# DAC.net
KiCad netlist of a schematic drawn in Altium Designer
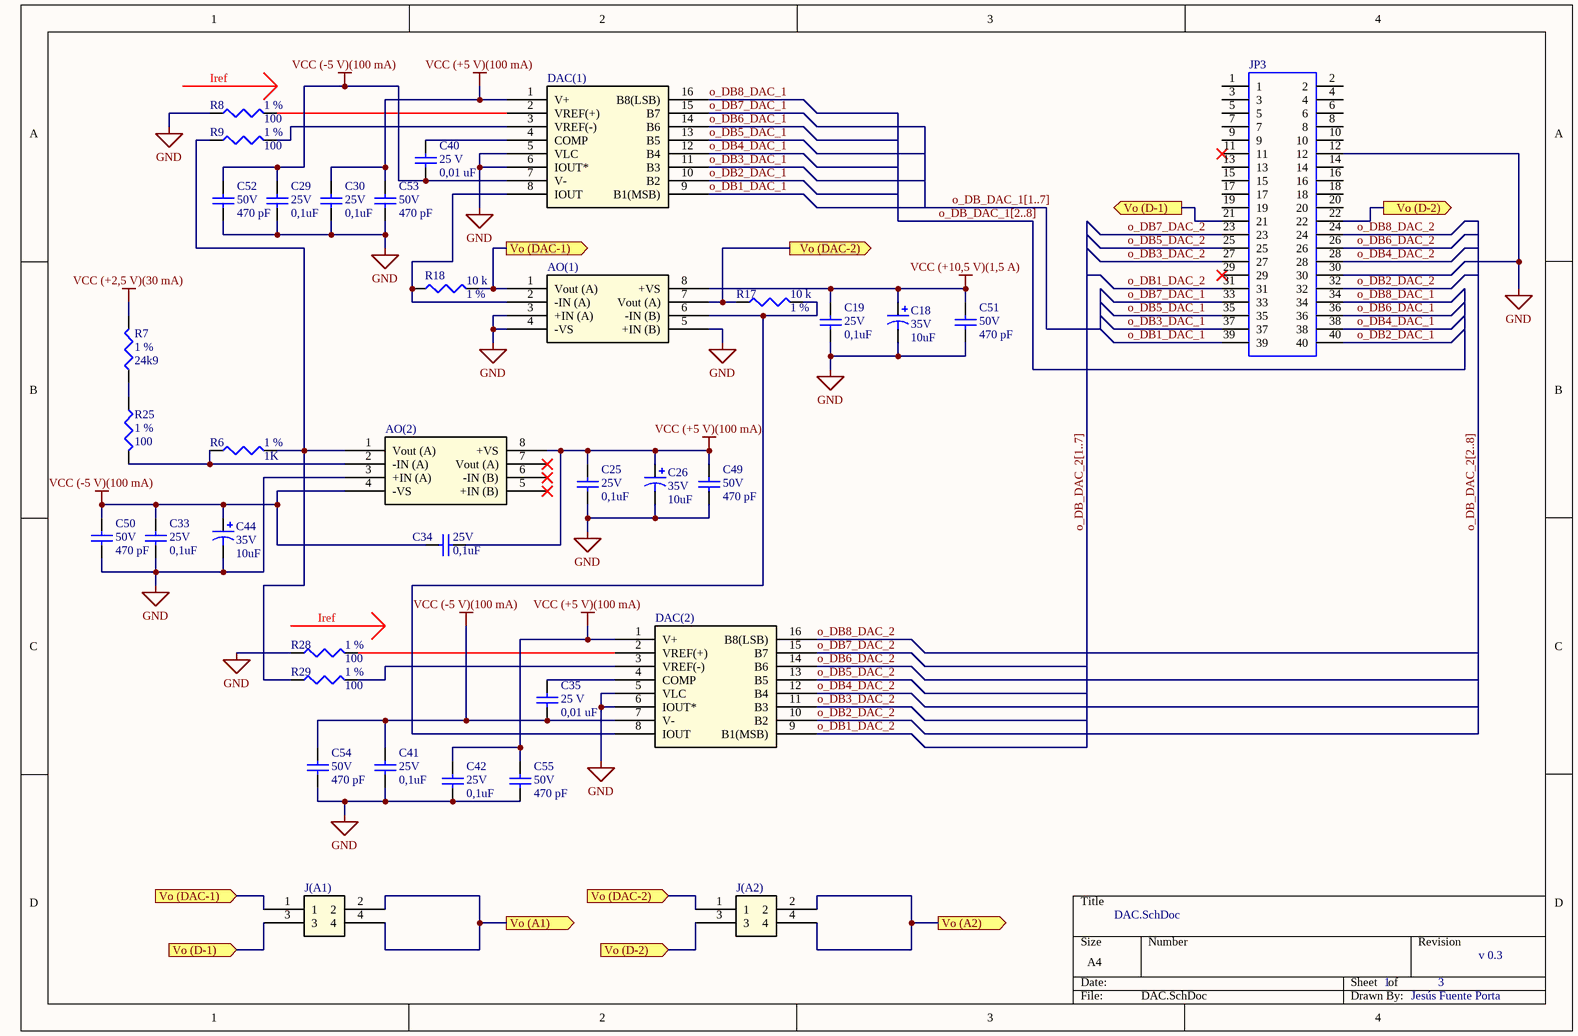
[diagram p0: DAC.SchDoc]

(export (version "E")
  (design (tool "Eeschema 10.0.6"))
  (components
    (comp (ref "AO(1)")
      (value "Part Number: AD8028ARZ")
      (footprint "AD8028ARZ - (R_8-M)")
      (fields
        (field (name "MANUFACTURER_PART_NUMBER") "AD8028ARZ")
        (field (name "COPYRIGHT") "Copyright (C) 2018 Accelerated Designs. All rights reserved")
      )
      (libsource (lib "ADC Library") (part "AD8028ARZ"))
    )
    (comp (ref "AO(2)")
      (value "Part Number: AD8028ARZ")
      (footprint "AD8028ARZ - (R_8-M)")
      (fields
        (field (name "MANUFACTURER_PART_NUMBER") "AD8028ARZ")
        (field (name "COPYRIGHT") "Copyright (C) 2018 Accelerated Designs. All rights reserved")
      )
      (libsource (lib "ADC Library") (part "AD8028ARZ"))
    )
    (comp (ref "C18")
      (value "35V")
      (footprint "EEE1VA100WR")
      (fields (field (name "ALTIUM_VALUE") "10uF") (field (name "PUBLISHER") "Altium Limited"))
      (libsource (lib "Miscellaneous Devices") (part "Cap Pol3"))
    )
    (comp (ref "C19")
      (value "25V")
      (footprint "1206 [Métrica 3216]")
      (fields (field (name "ALTIUM_VALUE") "0,1uF") (field (name "PUBLISHER") "Altium Limited"))
      (libsource (lib "Miscellaneous Devices") (part "Cap Semi"))
    )
    (comp (ref "C25")
      (value "25V")
      (footprint "1206 [Métrica 3216]")
      (fields (field (name "ALTIUM_VALUE") "0,1uF") (field (name "PUBLISHER") "Altium Limited"))
      (libsource (lib "Miscellaneous Devices") (part "Cap Semi"))
    )
    (comp (ref "C26")
      (value "35V")
      (footprint "EEE1VA100WR")
      (fields (field (name "ALTIUM_VALUE") "10uF") (field (name "PUBLISHER") "Altium Limited"))
      (libsource (lib "Miscellaneous Devices") (part "Cap Pol3"))
    )
    (comp (ref "C29")
      (value "25V")
      (footprint "1206 [Métrica 3216]")
      (fields (field (name "ALTIUM_VALUE") "0,1uF") (field (name "PUBLISHER") "Altium Limited"))
      (libsource (lib "Miscellaneous Devices") (part "Cap Semi"))
    )
    (comp (ref "C30")
      (value "25V")
      (footprint "1206 [Métrica 3216]")
      (fields (field (name "ALTIUM_VALUE") "0,1uF") (field (name "PUBLISHER") "Altium Limited"))
      (libsource (lib "Miscellaneous Devices") (part "Cap Semi"))
    )
    (comp (ref "C33")
      (value "25V")
      (footprint "1206 [Métrica 3216]")
      (fields (field (name "ALTIUM_VALUE") "0,1uF") (field (name "PUBLISHER") "Altium Limited"))
      (libsource (lib "Miscellaneous Devices") (part "Cap Semi"))
    )
    (comp (ref "C34")
      (value "25V")
      (footprint "1206 [Métrica 3216]")
      (fields (field (name "ALTIUM_VALUE") "0,1uF") (field (name "PUBLISHER") "Altium Limited"))
      (libsource (lib "Miscellaneous Devices") (part "Cap Semi"))
    )
    (comp (ref "C35")
      (value "25 V")
      (footprint "1206 [Métrica 3216]")
      (fields (field (name "ALTIUM_VALUE") "0,01 uF") (field (name "PUBLISHER") "Altium Limited"))
      (libsource (lib "Miscellaneous Devices") (part "Cap Semi"))
    )
    (comp (ref "C40")
      (value "25 V")
      (footprint "1206 [Métrica 3216]")
      (fields (field (name "ALTIUM_VALUE") "0,01 uF") (field (name "PUBLISHER") "Altium Limited"))
      (libsource (lib "Miscellaneous Devices") (part "Cap Semi"))
    )
    (comp (ref "C41")
      (value "25V")
      (footprint "1206 [Métrica 3216]")
      (fields (field (name "ALTIUM_VALUE") "0,1uF") (field (name "PUBLISHER") "Altium Limited"))
      (libsource (lib "Miscellaneous Devices") (part "Cap Semi"))
    )
    (comp (ref "C42")
      (value "25V")
      (footprint "1206 [Métrica 3216]")
      (fields (field (name "ALTIUM_VALUE") "0,1uF") (field (name "PUBLISHER") "Altium Limited"))
      (libsource (lib "Miscellaneous Devices") (part "Cap Semi"))
    )
    (comp (ref "C44")
      (value "35V")
      (footprint "EEE1VA100WR")
      (fields (field (name "ALTIUM_VALUE") "10uF") (field (name "PUBLISHER") "Altium Limited"))
      (libsource (lib "Miscellaneous Devices") (part "Cap Pol3"))
    )
    (comp (ref "C49")
      (value "50V")
      (footprint "1206 [Métrica 3216]")
      (fields (field (name "ALTIUM_VALUE") "470 pF") (field (name "PUBLISHER") "Altium Limited"))
      (libsource (lib "Miscellaneous Devices") (part "Cap Semi"))
    )
    (comp (ref "C50")
      (value "50V")
      (footprint "1206 [Métrica 3216]")
      (fields (field (name "ALTIUM_VALUE") "470 pF") (field (name "PUBLISHER") "Altium Limited"))
      (libsource (lib "Miscellaneous Devices") (part "Cap Semi"))
    )
    (comp (ref "C51")
      (value "50V")
      (footprint "1206 [Métrica 3216]")
      (fields (field (name "ALTIUM_VALUE") "470 pF") (field (name "PUBLISHER") "Altium Limited"))
      (libsource (lib "Miscellaneous Devices") (part "Cap Semi"))
    )
    (comp (ref "C52")
      (value "50V")
      (footprint "1206 [Métrica 3216]")
      (fields (field (name "ALTIUM_VALUE") "470 pF") (field (name "PUBLISHER") "Altium Limited"))
      (libsource (lib "Miscellaneous Devices") (part "Cap Semi"))
    )
    (comp (ref "C53")
      (value "50V")
      (footprint "1206 [Métrica 3216]")
      (fields (field (name "ALTIUM_VALUE") "470 pF") (field (name "PUBLISHER") "Altium Limited"))
      (libsource (lib "Miscellaneous Devices") (part "Cap Semi"))
    )
    (comp (ref "C54")
      (value "50V")
      (footprint "1206 [Métrica 3216]")
      (fields (field (name "ALTIUM_VALUE") "470 pF") (field (name "PUBLISHER") "Altium Limited"))
      (libsource (lib "Miscellaneous Devices") (part "Cap Semi"))
    )
    (comp (ref "C55")
      (value "50V")
      (footprint "1206 [Métrica 3216]")
      (fields (field (name "ALTIUM_VALUE") "470 pF") (field (name "PUBLISHER") "Altium Limited"))
      (libsource (lib "Miscellaneous Devices") (part "Cap Semi"))
    )
    (comp (ref "DAC(1)")
      (value "Part Number: DAC08ESZ")
      (footprint "DAC08ESZ_(R_16-M)")
      (description "DAC08ESZ -  Convertidor de Señal Digital a Analógica, 8 bit, ± 4.5V a ± 18V, NSOIC, 16 Pines")
      (fields
        (field (name "MANUFACTURER_PART_NUMBER") "DAC08ESZ")
        (field (name "COPYRIGHT") "Copyright (C) 2018 Accelerated Designs. All rights reserved")
      )
      (libsource (lib "ADC Library") (part "DAC08ESZ"))
    )
    (comp (ref "DAC(2)")
      (value "Part Number: DAC08ESZ")
      (footprint "DAC08ESZ_(R_16-M)")
      (description "DAC08ESZ -  Convertidor de Señal Digital a Analógica, 8 bit, ± 4.5V a ± 18V, NSOIC, 16 Pines")
      (fields
        (field (name "MANUFACTURER_PART_NUMBER") "DAC08ESZ")
        (field (name "COPYRIGHT") "Copyright (C) 2018 Accelerated Designs. All rights reserved")
      )
      (libsource (lib "ADC Library") (part "DAC08ESZ"))
    )
    (comp (ref "J(A1)")
      (value "TMM-102-01-G-D00 (2 connectors)")
      (footprint "TMM-102-01-G-D00 (2 connectors)")
      (fields
        (field (name "MANUFACTURER_PART_NUMBER") "TMM-102-01-L-D-SM")
        (field (name "COPYRIGHT") "Copyright (C) 2018 Accelerated Designs. All rights reserved")
      )
      (libsource (lib "ADC Library_Schematic Symbols") (part "TMM-102-01-G-D00 (2 connectors)"))
    )
    (comp (ref "J(A2)")
      (value "TMM-102-01-G-D00 (2 connectors)")
      (footprint "TMM-102-01-G-D00 (2 connectors)")
      (fields
        (field (name "MANUFACTURER_PART_NUMBER") "TMM-102-01-L-D-SM")
        (field (name "COPYRIGHT") "Copyright (C) 2018 Accelerated Designs. All rights reserved")
      )
      (libsource (lib "ADC Library_Schematic Symbols") (part "TMM-102-01-G-D00 (2 connectors)"))
    )
    (comp (ref "JP3")
      (value "IDC Connector_40p")
      (footprint "IDC Connector - 40 pins")
      (fields (field (name "RS PART NUMBER") "6257296"))
      (libsource (lib "ADC Library") (part "IDC Connector_40p"))
    )
    (comp (ref "R6")
      (value "1 %")
      (footprint "1206 [Métrica 3216]")
      (fields (field (name "ALTIUM_VALUE") "1K") (field (name "PUBLISHER") "Altium Limited"))
      (libsource (lib "Miscellaneous Devices") (part "Res3"))
    )
    (comp (ref "R7")
      (value "1 %")
      (footprint "1206 [Métrica 3216]")
      (fields (field (name "ALTIUM_VALUE") "24k9") (field (name "PUBLISHER") "Altium Limited"))
      (libsource (lib "Miscellaneous Devices") (part "Res3"))
    )
    (comp (ref "R8")
      (value "1 %")
      (footprint "1206 [Métrica 3216]")
      (fields (field (name "ALTIUM_VALUE") "100") (field (name "PUBLISHER") "Altium Limited"))
      (libsource (lib "Miscellaneous Devices") (part "Res3"))
    )
    (comp (ref "R9")
      (value "1 %")
      (footprint "1206 [Métrica 3216]")
      (fields (field (name "ALTIUM_VALUE") "100") (field (name "PUBLISHER") "Altium Limited"))
      (libsource (lib "Miscellaneous Devices") (part "Res3"))
    )
    (comp (ref "R17")
      (value "1 %")
      (footprint "1206 [Métrica 3216]")
      (fields (field (name "ALTIUM_VALUE") "10 k") (field (name "PUBLISHER") "Altium Limited"))
      (libsource (lib "Miscellaneous Devices") (part "Res3"))
    )
    (comp (ref "R18")
      (value "1 %")
      (footprint "1206 [Métrica 3216]")
      (fields (field (name "ALTIUM_VALUE") "10 k") (field (name "PUBLISHER") "Altium Limited"))
      (libsource (lib "Miscellaneous Devices") (part "Res3"))
    )
    (comp (ref "R25")
      (value "1 %")
      (footprint "1206 [Métrica 3216]")
      (fields (field (name "ALTIUM_VALUE") "100") (field (name "PUBLISHER") "Altium Limited"))
      (libsource (lib "Miscellaneous Devices") (part "Res3"))
    )
    (comp (ref "R28")
      (value "1 %")
      (footprint "1206 [Métrica 3216]")
      (fields (field (name "ALTIUM_VALUE") "100") (field (name "PUBLISHER") "Altium Limited"))
      (libsource (lib "Miscellaneous Devices") (part "Res3"))
    )
    (comp (ref "R29")
      (value "1 %")
      (footprint "1206 [Métrica 3216]")
      (fields (field (name "ALTIUM_VALUE") "100") (field (name "PUBLISHER") "Altium Limited"))
      (libsource (lib "Miscellaneous Devices") (part "Res3"))
    )
  )
  (nets
    (net (code "17") (name "/Vo (A1)") (class "Default")
      (node (ref "J(A1)") (pin "2") (pinfunction "2_2") (pintype "passive"))
      (node (ref "J(A1)") (pin "4") (pinfunction "4_4") (pintype "passive"))
    )
    (net (code "18") (name "/Vo (A2)") (class "Default")
      (node (ref "J(A2)") (pin "2") (pinfunction "2_2") (pintype "passive"))
      (node (ref "J(A2)") (pin "4") (pinfunction "4_4") (pintype "passive"))
    )
    (net (code "19") (name "/Vo (D-1)") (class "Default")
      (node (ref "J(A1)") (pin "3") (pinfunction "3_3") (pintype "passive"))
      (node (ref "JP3") (pin "21") (pinfunction "21_21") (pintype "passive"))
    )
    (net (code "20") (name "/Vo (D-2)") (class "Default")
      (node (ref "J(A2)") (pin "3") (pinfunction "3_3") (pintype "passive"))
      (node (ref "JP3") (pin "22") (pinfunction "22_22") (pintype "passive"))
    )
    (net (code "21") (name "/Vo (DAC-1)") (class "Default")
      (node (ref "AO(1)") (pin "1") (pinfunction "Vout_(A)_1") (pintype "passive"))
      (node (ref "J(A1)") (pin "1") (pinfunction "1_1") (pintype "passive"))
      (node (ref "R18") (pin "2") (pinfunction "2_2") (pintype "passive"))
    )
    (net (code "22") (name "/Vo (DAC-2)") (class "Default")
      (node (ref "AO(1)") (pin "7") (pinfunction "Vout_(A)_7") (pintype "passive"))
      (node (ref "J(A2)") (pin "1") (pinfunction "1_1") (pintype "passive"))
      (node (ref "R17") (pin "1") (pinfunction "1_1") (pintype "passive"))
    )
    (net (code "23") (name "/o_DB1_DAC_1") (class "Default")
      (node (ref "DAC(1)") (pin "9") (pinfunction "B1(MSB)_9") (pintype "passive"))
      (node (ref "JP3") (pin "39") (pinfunction "39_39") (pintype "passive"))
    )
    (net (code "24") (name "/o_DB1_DAC_2") (class "Default")
      (node (ref "DAC(2)") (pin "9") (pinfunction "B1(MSB)_9") (pintype "passive"))
      (node (ref "JP3") (pin "31") (pinfunction "31_31") (pintype "passive"))
    )
    (net (code "25") (name "/o_DB2_DAC_1") (class "Default")
      (node (ref "DAC(1)") (pin "10") (pinfunction "B2_10") (pintype "passive"))
      (node (ref "JP3") (pin "40") (pinfunction "40_40") (pintype "passive"))
    )
    (net (code "26") (name "/o_DB2_DAC_2") (class "Default")
      (node (ref "DAC(2)") (pin "10") (pinfunction "B2_10") (pintype "passive"))
      (node (ref "JP3") (pin "32") (pinfunction "32_32") (pintype "passive"))
    )
    (net (code "27") (name "/o_DB3_DAC_1") (class "Default")
      (node (ref "DAC(1)") (pin "11") (pinfunction "B3_11") (pintype "passive"))
      (node (ref "JP3") (pin "37") (pinfunction "37_37") (pintype "passive"))
    )
    (net (code "28") (name "/o_DB3_DAC_2") (class "Default")
      (node (ref "DAC(2)") (pin "11") (pinfunction "B3_11") (pintype "passive"))
      (node (ref "JP3") (pin "27") (pinfunction "27_27") (pintype "passive"))
    )
    (net (code "29") (name "/o_DB4_DAC_1") (class "Default")
      (node (ref "DAC(1)") (pin "12") (pinfunction "B4_12") (pintype "passive"))
      (node (ref "JP3") (pin "38") (pinfunction "38_38") (pintype "passive"))
    )
    (net (code "30") (name "/o_DB4_DAC_2") (class "Default")
      (node (ref "DAC(2)") (pin "12") (pinfunction "B4_12") (pintype "passive"))
      (node (ref "JP3") (pin "28") (pinfunction "28_28") (pintype "passive"))
    )
    (net (code "31") (name "/o_DB5_DAC_1") (class "Default")
      (node (ref "DAC(1)") (pin "13") (pinfunction "B5_13") (pintype "passive"))
      (node (ref "JP3") (pin "35") (pinfunction "35_35") (pintype "passive"))
    )
    (net (code "32") (name "/o_DB5_DAC_2") (class "Default")
      (node (ref "DAC(2)") (pin "13") (pinfunction "B5_13") (pintype "passive"))
      (node (ref "JP3") (pin "25") (pinfunction "25_25") (pintype "passive"))
    )
    (net (code "33") (name "/o_DB6_DAC_1") (class "Default")
      (node (ref "DAC(1)") (pin "14") (pinfunction "B6_14") (pintype "passive"))
      (node (ref "JP3") (pin "36") (pinfunction "36_36") (pintype "passive"))
    )
    (net (code "34") (name "/o_DB6_DAC_2") (class "Default")
      (node (ref "DAC(2)") (pin "14") (pinfunction "B6_14") (pintype "passive"))
      (node (ref "JP3") (pin "26") (pinfunction "26_26") (pintype "passive"))
    )
    (net (code "35") (name "/o_DB7_DAC_1") (class "Default")
      (node (ref "DAC(1)") (pin "15") (pinfunction "B7_15") (pintype "passive"))
      (node (ref "JP3") (pin "33") (pinfunction "33_33") (pintype "passive"))
    )
    (net (code "36") (name "/o_DB7_DAC_2") (class "Default")
      (node (ref "DAC(2)") (pin "15") (pinfunction "B7_15") (pintype "passive"))
      (node (ref "JP3") (pin "23") (pinfunction "23_23") (pintype "passive"))
    )
    (net (code "37") (name "/o_DB8_DAC_1") (class "Default")
      (node (ref "DAC(1)") (pin "16") (pinfunction "B8(LSB)_16") (pintype "passive"))
      (node (ref "JP3") (pin "34") (pinfunction "34_34") (pintype "passive"))
    )
    (net (code "38") (name "/o_DB8_DAC_2") (class "Default")
      (node (ref "DAC(2)") (pin "16") (pinfunction "B8(LSB)_16") (pintype "passive"))
      (node (ref "JP3") (pin "24") (pinfunction "24_24") (pintype "passive"))
    )
    (net (code "43") (name "GND") (class "Default")
      (node (ref "AO(1)") (pin "3") (pinfunction "+IN_(A)_3") (pintype "passive"))
      (node (ref "AO(1)") (pin "4") (pinfunction "-VS_4") (pintype "power_in"))
      (node (ref "AO(1)") (pin "5") (pinfunction "+IN_(B)_5") (pintype "passive"))
      (node (ref "AO(2)") (pin "3") (pinfunction "+IN_(A)_3") (pintype "passive"))
      (node (ref "C18") (pin "2") (pinfunction "2_2") (pintype "passive"))
      (node (ref "C19") (pin "1") (pinfunction "1_1") (pintype "passive"))
      (node (ref "C25") (pin "1") (pinfunction "1_1") (pintype "passive"))
      (node (ref "C26") (pin "2") (pinfunction "2_2") (pintype "passive"))
      (node (ref "C29") (pin "1") (pinfunction "1_1") (pintype "passive"))
      (node (ref "C30") (pin "1") (pinfunction "1_1") (pintype "passive"))
      (node (ref "C33") (pin "1") (pinfunction "1_1") (pintype "passive"))
      (node (ref "C41") (pin "1") (pinfunction "1_1") (pintype "passive"))
      (node (ref "C42") (pin "1") (pinfunction "1_1") (pintype "passive"))
      (node (ref "C44") (pin "2") (pinfunction "2_2") (pintype "passive"))
      (node (ref "C49") (pin "1") (pinfunction "1_1") (pintype "passive"))
      (node (ref "C50") (pin "1") (pinfunction "1_1") (pintype "passive"))
      (node (ref "C51") (pin "1") (pinfunction "1_1") (pintype "passive"))
      (node (ref "C52") (pin "1") (pinfunction "1_1") (pintype "passive"))
      (node (ref "C53") (pin "1") (pinfunction "1_1") (pintype "passive"))
      (node (ref "C54") (pin "1") (pinfunction "1_1") (pintype "passive"))
      (node (ref "C55") (pin "1") (pinfunction "1_1") (pintype "passive"))
      (node (ref "DAC(1)") (pin "5") (pinfunction "VLC_5") (pintype "passive"))
      (node (ref "DAC(1)") (pin "6") (pinfunction "IOUT*_6") (pintype "passive"))
      (node (ref "DAC(2)") (pin "5") (pinfunction "VLC_5") (pintype "passive"))
      (node (ref "DAC(2)") (pin "6") (pinfunction "IOUT*_6") (pintype "passive"))
      (node (ref "JP3") (pin "12") (pinfunction "12_12") (pintype "passive"))
      (node (ref "JP3") (pin "30") (pinfunction "30_30") (pintype "passive"))
      (node (ref "R28") (pin "1") (pinfunction "1_1") (pintype "passive"))
      (node (ref "R8") (pin "1") (pinfunction "1_1") (pintype "passive"))
    )
    (net (code "44") (name "Net-(AO(1)--IN_(A))") (class "Default")
      (node (ref "AO(1)") (pin "2") (pinfunction "-IN_(A)_2") (pintype "passive"))
      (node (ref "DAC(1)") (pin "8") (pinfunction "IOUT_8") (pintype "passive"))
      (node (ref "R18") (pin "1") (pinfunction "1_1") (pintype "passive"))
    )
    (net (code "45") (name "Net-(AO(1)--IN_(B))") (class "Default")
      (node (ref "AO(1)") (pin "6") (pinfunction "-IN_(B)_6") (pintype "passive"))
      (node (ref "DAC(2)") (pin "8") (pinfunction "IOUT_8") (pintype "passive"))
      (node (ref "R17") (pin "2") (pinfunction "2_2") (pintype "passive"))
    )
    (net (code "46") (name "Net-(AO(2)--IN_(A))") (class "Default")
      (node (ref "AO(2)") (pin "2") (pinfunction "-IN_(A)_2") (pintype "passive"))
      (node (ref "R25") (pin "2") (pinfunction "2_2") (pintype "passive"))
      (node (ref "R6") (pin "1") (pinfunction "1_1") (pintype "passive"))
    )
    (net (code "47") (name "Net-(AO(2)-Vout_(A)-Pad1)") (class "Default")
      (node (ref "AO(2)") (pin "1") (pinfunction "Vout_(A)_1") (pintype "passive"))
      (node (ref "R29") (pin "1") (pinfunction "1_1") (pintype "passive"))
      (node (ref "R6") (pin "2") (pinfunction "2_2") (pintype "passive"))
      (node (ref "R9") (pin "1") (pinfunction "1_1") (pintype "passive"))
    )
    (net (code "48") (name "Net-(DAC(1)-COMP)") (class "Default")
      (node (ref "C40") (pin "2") (pinfunction "2_2") (pintype "passive"))
      (node (ref "DAC(1)") (pin "4") (pinfunction "COMP_4") (pintype "passive"))
    )
    (net (code "49") (name "Net-(DAC(1)-VREF(+))") (class "Default")
      (node (ref "DAC(1)") (pin "2") (pinfunction "VREF(+)_2") (pintype "passive"))
      (node (ref "R8") (pin "2") (pinfunction "2_2") (pintype "passive"))
    )
    (net (code "50") (name "Net-(DAC(1)-VREF(-))") (class "Default")
      (node (ref "DAC(1)") (pin "3") (pinfunction "VREF(-)_3") (pintype "passive"))
      (node (ref "R9") (pin "2") (pinfunction "2_2") (pintype "passive"))
    )
    (net (code "51") (name "Net-(DAC(2)-COMP)") (class "Default")
      (node (ref "C35") (pin "2") (pinfunction "2_2") (pintype "passive"))
      (node (ref "DAC(2)") (pin "4") (pinfunction "COMP_4") (pintype "passive"))
    )
    (net (code "52") (name "Net-(DAC(2)-VREF(+))") (class "Default")
      (node (ref "DAC(2)") (pin "2") (pinfunction "VREF(+)_2") (pintype "passive"))
      (node (ref "R28") (pin "2") (pinfunction "2_2") (pintype "passive"))
    )
    (net (code "53") (name "Net-(DAC(2)-VREF(-))") (class "Default")
      (node (ref "DAC(2)") (pin "3") (pinfunction "VREF(-)_3") (pintype "passive"))
      (node (ref "R29") (pin "2") (pinfunction "2_2") (pintype "passive"))
    )
    (net (code "54") (name "Net-(R25-Pad1)") (class "Default")
      (node (ref "R25") (pin "1") (pinfunction "1_1") (pintype "passive"))
      (node (ref "R7") (pin "1") (pinfunction "1_1") (pintype "passive"))
    )
    (net (code "55") (name "VCC (+2,5 V)(30 mA)") (class "Default")
      (node (ref "R7") (pin "2") (pinfunction "2_2") (pintype "passive"))
    )
    (net (code "56") (name "VCC (+5 V)(100 mA)") (class "Default")
      (node (ref "AO(2)") (pin "8") (pinfunction "+VS_8") (pintype "passive"))
      (node (ref "C25") (pin "2") (pinfunction "2_2") (pintype "passive"))
      (node (ref "C26") (pin "1") (pinfunction "1_1") (pintype "passive"))
      (node (ref "C30") (pin "2") (pinfunction "2_2") (pintype "passive"))
      (node (ref "C34") (pin "1") (pinfunction "1_1") (pintype "passive"))
      (node (ref "C42") (pin "2") (pinfunction "2_2") (pintype "passive"))
      (node (ref "C49") (pin "2") (pinfunction "2_2") (pintype "passive"))
      (node (ref "C53") (pin "2") (pinfunction "2_2") (pintype "passive"))
      (node (ref "C55") (pin "2") (pinfunction "2_2") (pintype "passive"))
      (node (ref "DAC(1)") (pin "1") (pinfunction "V+_1") (pintype "power_in"))
      (node (ref "DAC(2)") (pin "1") (pinfunction "V+_1") (pintype "power_in"))
    )
    (net (code "57") (name "VCC (+10,5 V)(1,5 A)") (class "Default")
      (node (ref "AO(1)") (pin "8") (pinfunction "+VS_8") (pintype "passive"))
      (node (ref "C18") (pin "1") (pinfunction "1_1") (pintype "passive"))
      (node (ref "C19") (pin "2") (pinfunction "2_2") (pintype "passive"))
      (node (ref "C51") (pin "2") (pinfunction "2_2") (pintype "passive"))
    )
    (net (code "58") (name "VCC (-5 V)(100 mA)") (class "Default")
      (node (ref "AO(2)") (pin "4") (pinfunction "-VS_4") (pintype "power_in"))
      (node (ref "C29") (pin "2") (pinfunction "2_2") (pintype "passive"))
      (node (ref "C33") (pin "2") (pinfunction "2_2") (pintype "passive"))
      (node (ref "C34") (pin "2") (pinfunction "2_2") (pintype "passive"))
      (node (ref "C35") (pin "1") (pinfunction "1_1") (pintype "passive"))
      (node (ref "C40") (pin "1") (pinfunction "1_1") (pintype "passive"))
      (node (ref "C41") (pin "2") (pinfunction "2_2") (pintype "passive"))
      (node (ref "C44") (pin "1") (pinfunction "1_1") (pintype "passive"))
      (node (ref "C50") (pin "2") (pinfunction "2_2") (pintype "passive"))
      (node (ref "C52") (pin "2") (pinfunction "2_2") (pintype "passive"))
      (node (ref "C54") (pin "2") (pinfunction "2_2") (pintype "passive"))
      (node (ref "DAC(1)") (pin "7") (pinfunction "V-_7") (pintype "power_in"))
      (node (ref "DAC(2)") (pin "7") (pinfunction "V-_7") (pintype "power_in"))
    )
    (net (code "59") (name "unconnected-(AO(2)-+IN_(B)-Pad5)") (class "Default")
      (node (ref "AO(2)") (pin "5") (pinfunction "+IN_(B)_5") (pintype "passive+no_connect"))
    )
    (net (code "60") (name "unconnected-(AO(2)--IN_(B)-Pad6)") (class "Default")
      (node (ref "AO(2)") (pin "6") (pinfunction "-IN_(B)_6") (pintype "passive+no_connect"))
    )
    (net (code "61") (name "unconnected-(AO(2)-Vout_(A)-Pad7)") (class "Default")
      (node (ref "AO(2)") (pin "7") (pinfunction "Vout_(A)_7") (pintype "passive+no_connect"))
    )
    (net (code "62") (name "unconnected-(JP3-Pad1)") (class "Default")
      (node (ref "JP3") (pin "1") (pinfunction "1_1") (pintype "passive"))
    )
    (net (code "63") (name "unconnected-(JP3-Pad2)") (class "Default")
      (node (ref "JP3") (pin "2") (pinfunction "2_2") (pintype "passive"))
    )
    (net (code "64") (name "unconnected-(JP3-Pad3)") (class "Default")
      (node (ref "JP3") (pin "3") (pinfunction "3_3") (pintype "passive"))
    )
    (net (code "65") (name "unconnected-(JP3-Pad4)") (class "Default")
      (node (ref "JP3") (pin "4") (pinfunction "4_4") (pintype "passive"))
    )
    (net (code "66") (name "unconnected-(JP3-Pad5)") (class "Default")
      (node (ref "JP3") (pin "5") (pinfunction "5_5") (pintype "passive"))
    )
    (net (code "67") (name "unconnected-(JP3-Pad6)") (class "Default")
      (node (ref "JP3") (pin "6") (pinfunction "6_6") (pintype "passive"))
    )
    (net (code "68") (name "unconnected-(JP3-Pad7)") (class "Default")
      (node (ref "JP3") (pin "7") (pinfunction "7_7") (pintype "passive"))
    )
    (net (code "69") (name "unconnected-(JP3-Pad8)") (class "Default")
      (node (ref "JP3") (pin "8") (pinfunction "8_8") (pintype "passive"))
    )
    (net (code "70") (name "unconnected-(JP3-Pad9)") (class "Default")
      (node (ref "JP3") (pin "9") (pinfunction "9_9") (pintype "passive"))
    )
    (net (code "71") (name "unconnected-(JP3-Pad10)") (class "Default")
      (node (ref "JP3") (pin "10") (pinfunction "10_10") (pintype "passive"))
    )
    (net (code "72") (name "unconnected-(JP3-Pad11)") (class "Default")
      (node (ref "JP3") (pin "11") (pinfunction "11_11") (pintype "passive+no_connect"))
    )
    (net (code "73") (name "unconnected-(JP3-Pad13)") (class "Default")
      (node (ref "JP3") (pin "13") (pinfunction "13_13") (pintype "passive"))
    )
    (net (code "74") (name "unconnected-(JP3-Pad14)") (class "Default")
      (node (ref "JP3") (pin "14") (pinfunction "14_14") (pintype "passive"))
    )
    (net (code "75") (name "unconnected-(JP3-Pad15)") (class "Default")
      (node (ref "JP3") (pin "15") (pinfunction "15_15") (pintype "passive"))
    )
    (net (code "76") (name "unconnected-(JP3-Pad16)") (class "Default")
      (node (ref "JP3") (pin "16") (pinfunction "16_16") (pintype "passive"))
    )
    (net (code "77") (name "unconnected-(JP3-Pad17)") (class "Default")
      (node (ref "JP3") (pin "17") (pinfunction "17_17") (pintype "passive"))
    )
    (net (code "78") (name "unconnected-(JP3-Pad18)") (class "Default")
      (node (ref "JP3") (pin "18") (pinfunction "18_18") (pintype "passive"))
    )
    (net (code "79") (name "unconnected-(JP3-Pad19)") (class "Default")
      (node (ref "JP3") (pin "19") (pinfunction "19_19") (pintype "passive"))
    )
    (net (code "80") (name "unconnected-(JP3-Pad20)") (class "Default")
      (node (ref "JP3") (pin "20") (pinfunction "20_20") (pintype "passive"))
    )
    (net (code "81") (name "unconnected-(JP3-Pad29)") (class "Default")
      (node (ref "JP3") (pin "29") (pinfunction "29_29") (pintype "passive+no_connect"))
    )
  )
)
